# AD8368.net
KiCad netlist of a schematic drawn in Altium Designer
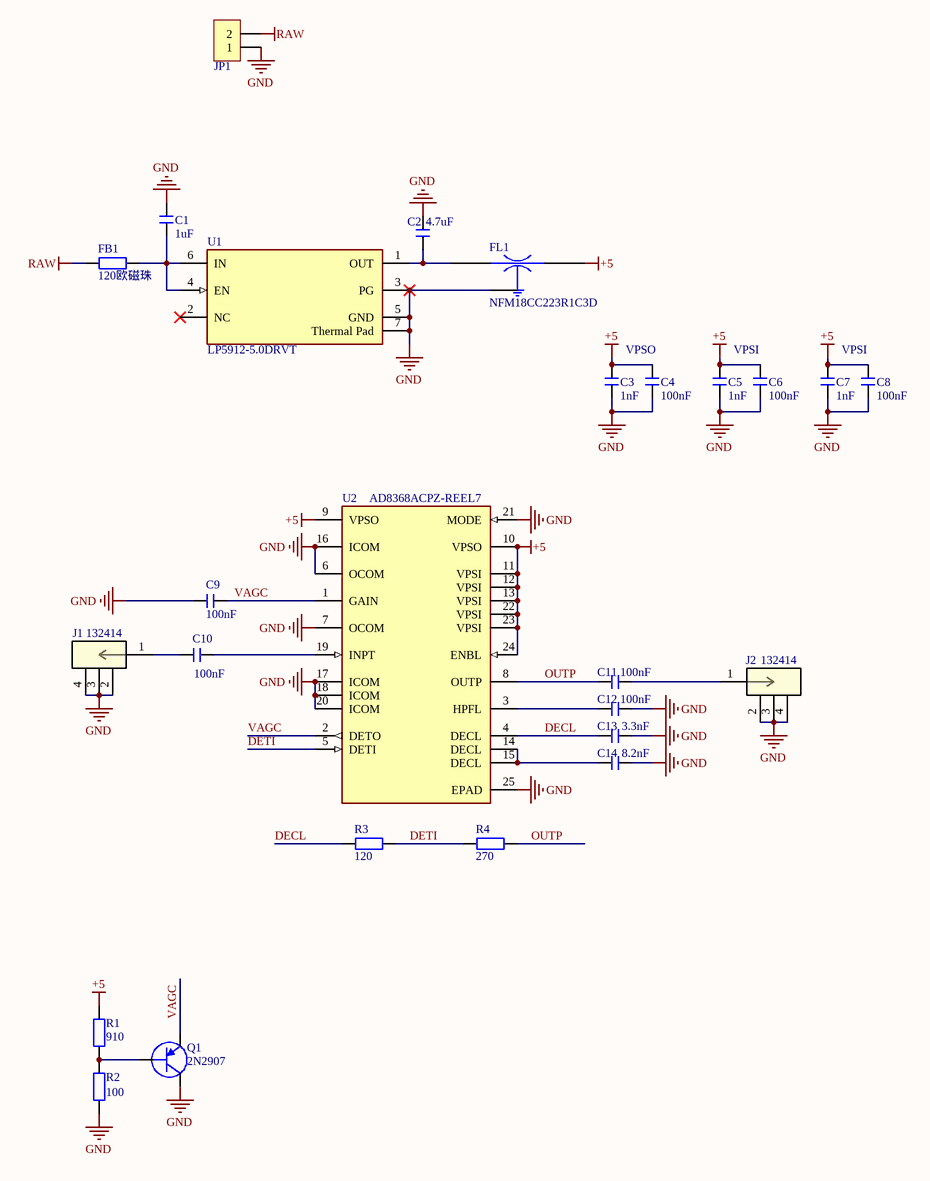
[diagram p0: AD8368.SchDoc]

(export (version "E")
  (design (tool "Eeschema 10.0.6"))
  (components
    (comp (ref "C1")
      (value "1uF")
      (footprint "C 0603_L")
      (description "贴片电容")
      (libsource (lib "01 - 电容-电阻-电感") (part "C"))
    )
    (comp (ref "C2")
      (value "4.7uF")
      (footprint "C 0603_L")
      (description "贴片电容")
      (libsource (lib "01 - 电容-电阻-电感") (part "C"))
    )
    (comp (ref "C3")
      (value "1nF")
      (footprint "C 0402_L")
      (description "贴片电容")
      (libsource (lib "01 - 电容-电阻-电感") (part "C"))
    )
    (comp (ref "C4")
      (value "100nF")
      (footprint "C 0402_L")
      (description "贴片电容")
      (libsource (lib "01 - 电容-电阻-电感") (part "C"))
    )
    (comp (ref "C5")
      (value "1nF")
      (footprint "C 0402_L")
      (description "贴片电容")
      (libsource (lib "01 - 电容-电阻-电感") (part "C"))
    )
    (comp (ref "C6")
      (value "100nF")
      (footprint "C 0402_L")
      (description "贴片电容")
      (libsource (lib "01 - 电容-电阻-电感") (part "C"))
    )
    (comp (ref "C7")
      (value "1nF")
      (footprint "C 0402_L")
      (description "贴片电容")
      (libsource (lib "01 - 电容-电阻-电感") (part "C"))
    )
    (comp (ref "C8")
      (value "100nF")
      (footprint "C 0402_L")
      (description "贴片电容")
      (libsource (lib "01 - 电容-电阻-电感") (part "C"))
    )
    (comp (ref "C9")
      (value "100nF")
      (footprint "C 0402_L")
      (description "贴片电容")
      (libsource (lib "01 - 电容-电阻-电感") (part "C"))
    )
    (comp (ref "C10")
      (value "100nF")
      (footprint "C 0402_L")
      (description "贴片电容")
      (libsource (lib "01 - 电容-电阻-电感") (part "C"))
    )
    (comp (ref "C11")
      (value "100nF")
      (footprint "C 0402_L")
      (description "贴片电容")
      (libsource (lib "01 - 电容-电阻-电感") (part "C"))
    )
    (comp (ref "C12")
      (value "100nF")
      (footprint "C 0402_L")
      (description "贴片电容")
      (libsource (lib "01 - 电容-电阻-电感") (part "C"))
    )
    (comp (ref "C13")
      (value "3.3nF")
      (footprint "C 0402_L")
      (description "贴片电容")
      (libsource (lib "01 - 电容-电阻-电感") (part "C"))
    )
    (comp (ref "C14")
      (value "8.2nF")
      (footprint "C 0402_L")
      (description "贴片电容")
      (libsource (lib "01 - 电容-电阻-电感") (part "C"))
    )
    (comp (ref "FB1")
      (value "120欧磁珠")
      (footprint "R 0603_L")
      (description "贴片电阻")
      (libsource (lib "01 - 电容-电阻-电感") (part "R"))
    )
    (comp (ref "FL1")
      (value "NFM18CC223R1C3D")
      (footprint "FIL_NFM18CC223R1C3D")
      (description "SMD Capacitor with Capacitance: 22000pF Tol. 20%. Rated Voltage: 16Vdc")
      (fields (field (name "MF") "Murata"))
      (libsource (lib "NFM18CC223R1C3D") (part "NFM18CC223R1C3D"))
    )
    (comp (ref "J1")
      (value "132414")
      (footprint "CONN_132414_AMP")
      (description "No Description Available")
      (fields (field (name "COPYRIGHT") "Copyright (C) 2022 Ultra Librarian. All rights reserved."))
      (libsource (lib "") (part "132414_1"))
    )
    (comp (ref "J2")
      (value "132414")
      (footprint "CONN_132414_AMP")
      (description "No Description Available")
      (fields (field (name "COPYRIGHT") "Copyright (C) 2022 Ultra Librarian. All rights reserved."))
      (libsource (lib "细针大偏脚SMA(用这个)") (part "132414"))
    )
    (comp (ref "JP1")
      (value "HDR-1X2")
      (footprint "KF2510-LI-2P")
      (description "2P接插件")
      (libsource (lib "18 - 接插件-脚距2.54mm (100mil) ") (part "Header 2"))
    )
    (comp (ref "Q1")
      (value "2N2907")
      (footprint "SOT23-3N")
      (description "PNP型三极管")
      (libsource (lib "02 - 二极管(LED)-三极管-整流桥") (part "2N-PNP"))
    )
    (comp (ref "R1")
      (value "910")
      (footprint "R 0402_L")
      (description "贴片电阻")
      (libsource (lib "01 - 电容-电阻-电感") (part "R"))
    )
    (comp (ref "R2")
      (value "100")
      (footprint "R 0402_L")
      (description "贴片电阻")
      (libsource (lib "01 - 电容-电阻-电感") (part "R"))
    )
    (comp (ref "R3")
      (value "120")
      (footprint "R 0603_L")
      (description "贴片电阻")
      (libsource (lib "01 - 电容-电阻-电感") (part "R"))
    )
    (comp (ref "R4")
      (value "270")
      (footprint "R 0603_L")
      (description "贴片电阻")
      (libsource (lib "01 - 电容-电阻-电感") (part "R"))
    )
    (comp (ref "U1")
      (value "LP5912-5.0DRVT")
      (footprint "FP-DRV0006A-MFG")
      (description "IC REG LINEAR  5.0V 500MA 6SON")
      (libsource (lib "LP5912") (part "LP5912"))
    )
    (comp (ref "U2")
      (value "AD8368ACPZ-REEL7")
      (footprint "FP-CP-24-7-IPC_C")
      (description "IC OPAMP VGA 1 CIRCUIT 24LFCSP")
      (libsource (lib "AD8368") (part "AD8368ACPZ-REEL7"))
    )
  )
  (nets
    (net (code "1") (name "+5") (class "Default")
      (node (ref "C3") (pin "2") (pinfunction "2_2") (pintype "passive"))
      (node (ref "C4") (pin "2") (pinfunction "2_2") (pintype "passive"))
      (node (ref "C5") (pin "2") (pinfunction "2_2") (pintype "passive"))
      (node (ref "C6") (pin "2") (pinfunction "2_2") (pintype "passive"))
      (node (ref "C7") (pin "2") (pinfunction "2_2") (pintype "passive"))
      (node (ref "C8") (pin "2") (pinfunction "2_2") (pintype "passive"))
      (node (ref "FL1") (pin "3") (pintype "passive"))
      (node (ref "R1") (pin "2") (pinfunction "2_2") (pintype "passive"))
      (node (ref "U2") (pin "10") (pinfunction "VPSO_10") (pintype "power_in"))
      (node (ref "U2") (pin "11") (pinfunction "VPSI_11") (pintype "power_in"))
      (node (ref "U2") (pin "12") (pinfunction "VPSI_12") (pintype "power_in"))
      (node (ref "U2") (pin "13") (pinfunction "VPSI_13") (pintype "power_in"))
      (node (ref "U2") (pin "22") (pinfunction "VPSI_22") (pintype "power_in"))
      (node (ref "U2") (pin "23") (pinfunction "VPSI_23") (pintype "power_in"))
      (node (ref "U2") (pin "24") (pinfunction "ENBL_24") (pintype "input"))
      (node (ref "U2") (pin "9") (pinfunction "VPSO_9") (pintype "power_in"))
    )
    (net (code "2") (name "/DECL") (class "Default")
      (node (ref "C13") (pin "1") (pinfunction "1_1") (pintype "passive"))
      (node (ref "R3") (pin "1") (pinfunction "1_1") (pintype "passive"))
      (node (ref "U2") (pin "4") (pinfunction "DECL_4") (pintype "passive"))
    )
    (net (code "3") (name "/DETI") (class "Default")
      (node (ref "R3") (pin "2") (pinfunction "2_2") (pintype "passive"))
      (node (ref "R4") (pin "1") (pinfunction "1_1") (pintype "passive"))
      (node (ref "U2") (pin "5") (pinfunction "DETI_5") (pintype "input"))
    )
    (net (code "4") (name "/OUTP") (class "Default")
      (node (ref "C11") (pin "1") (pinfunction "1_1") (pintype "passive"))
      (node (ref "R4") (pin "2") (pinfunction "2_2") (pintype "passive"))
      (node (ref "U2") (pin "8") (pinfunction "OUTP_8") (pintype "passive"))
    )
    (net (code "5") (name "/VAGC") (class "Default")
      (node (ref "C9") (pin "2") (pinfunction "2_2") (pintype "passive"))
      (node (ref "Q1") (pin "1") (pinfunction "E_1") (pintype "passive"))
      (node (ref "U2") (pin "1") (pinfunction "GAIN_1") (pintype "passive"))
      (node (ref "U2") (pin "2") (pinfunction "DETO_2") (pintype "output"))
    )
    (net (code "6") (name "GND") (class "Default")
      (node (ref "C1") (pin "2") (pinfunction "2_2") (pintype "passive"))
      (node (ref "C12") (pin "2") (pinfunction "2_2") (pintype "passive"))
      (node (ref "C13") (pin "2") (pinfunction "2_2") (pintype "passive"))
      (node (ref "C14") (pin "2") (pinfunction "2_2") (pintype "passive"))
      (node (ref "C2") (pin "2") (pinfunction "2_2") (pintype "passive"))
      (node (ref "C3") (pin "1") (pinfunction "1_1") (pintype "passive"))
      (node (ref "C4") (pin "1") (pinfunction "1_1") (pintype "passive"))
      (node (ref "C5") (pin "1") (pinfunction "1_1") (pintype "passive"))
      (node (ref "C6") (pin "1") (pinfunction "1_1") (pintype "passive"))
      (node (ref "C7") (pin "1") (pinfunction "1_1") (pintype "passive"))
      (node (ref "C8") (pin "1") (pinfunction "1_1") (pintype "passive"))
      (node (ref "C9") (pin "1") (pinfunction "1_1") (pintype "passive"))
      (node (ref "FL1") (pin "2") (pinfunction "GND_2") (pintype "power_in"))
      (node (ref "J1") (pin "2") (pinfunction "2_2") (pintype "passive"))
      (node (ref "J1") (pin "3") (pinfunction "3_3") (pintype "passive"))
      (node (ref "J1") (pin "4") (pinfunction "4_4") (pintype "passive"))
      (node (ref "J2") (pin "2") (pinfunction "2_2") (pintype "passive"))
      (node (ref "J2") (pin "3") (pinfunction "3_3") (pintype "passive"))
      (node (ref "J2") (pin "4") (pinfunction "4_4") (pintype "passive"))
      (node (ref "JP1") (pin "1") (pinfunction "1_1") (pintype "passive"))
      (node (ref "Q1") (pin "3") (pinfunction "C_3") (pintype "passive"))
      (node (ref "R2") (pin "1") (pinfunction "1_1") (pintype "passive"))
      (node (ref "U1") (pin "3") (pinfunction "PG_3") (pintype "open_collector"))
      (node (ref "U1") (pin "5") (pinfunction "GND_5") (pintype "power_in"))
      (node (ref "U1") (pin "7") (pinfunction "Thermal_Pad_7") (pintype "power_in"))
      (node (ref "U2") (pin "16") (pinfunction "ICOM_16") (pintype "passive"))
      (node (ref "U2") (pin "17") (pinfunction "ICOM_17") (pintype "passive"))
      (node (ref "U2") (pin "18") (pinfunction "ICOM_18") (pintype "passive"))
      (node (ref "U2") (pin "20") (pinfunction "ICOM_20") (pintype "passive"))
      (node (ref "U2") (pin "21") (pinfunction "MODE_21") (pintype "input"))
      (node (ref "U2") (pin "25") (pinfunction "EPAD_25") (pintype "passive"))
      (node (ref "U2") (pin "6") (pinfunction "OCOM_6") (pintype "passive"))
      (node (ref "U2") (pin "7") (pinfunction "OCOM_7") (pintype "passive"))
    )
    (net (code "7") (name "Net-(C10-Pad1)") (class "Default")
      (node (ref "C10") (pin "1") (pinfunction "1_1") (pintype "passive"))
      (node (ref "J1") (pin "1") (pinfunction "1_1") (pintype "passive"))
    )
    (net (code "8") (name "Net-(C11-Pad2)") (class "Default")
      (node (ref "C11") (pin "2") (pinfunction "2_2") (pintype "passive"))
      (node (ref "J2") (pin "1") (pinfunction "1_1") (pintype "passive"))
    )
    (net (code "9") (name "Net-(C14-Pad1)") (class "Default")
      (node (ref "C14") (pin "1") (pinfunction "1_1") (pintype "passive"))
      (node (ref "U2") (pin "14") (pinfunction "DECL_14") (pintype "passive"))
      (node (ref "U2") (pin "15") (pinfunction "DECL_15") (pintype "passive"))
    )
    (net (code "10") (name "Net-(Q1-B)") (class "Default")
      (node (ref "Q1") (pin "2") (pinfunction "B_2") (pintype "passive"))
      (node (ref "R1") (pin "1") (pinfunction "1_1") (pintype "passive"))
      (node (ref "R2") (pin "2") (pinfunction "2_2") (pintype "passive"))
    )
    (net (code "11") (name "Net-(U1-EN)") (class "Default")
      (node (ref "C1") (pin "1") (pinfunction "1_1") (pintype "passive"))
      (node (ref "FB1") (pin "2") (pinfunction "2_2") (pintype "passive"))
      (node (ref "U1") (pin "4") (pinfunction "EN_4") (pintype "input"))
      (node (ref "U1") (pin "6") (pinfunction "IN_6") (pintype "power_in"))
    )
    (net (code "12") (name "Net-(U1-OUT)") (class "Default")
      (node (ref "C2") (pin "1") (pinfunction "1_1") (pintype "passive"))
      (node (ref "FL1") (pin "1") (pintype "passive"))
      (node (ref "U1") (pin "1") (pinfunction "OUT_1") (pintype "power_in"))
    )
    (net (code "13") (name "Net-(U2-HPFL)") (class "Default")
      (node (ref "C12") (pin "1") (pinfunction "1_1") (pintype "passive"))
      (node (ref "U2") (pin "3") (pinfunction "HPFL_3") (pintype "passive"))
    )
    (net (code "14") (name "Net-(U2-INPT)") (class "Default")
      (node (ref "C10") (pin "2") (pinfunction "2_2") (pintype "passive"))
      (node (ref "U2") (pin "19") (pinfunction "INPT_19") (pintype "input"))
    )
    (net (code "15") (name "RAW") (class "Default")
      (node (ref "FB1") (pin "1") (pinfunction "1_1") (pintype "passive"))
      (node (ref "JP1") (pin "2") (pinfunction "2_2") (pintype "passive"))
    )
    (net (code "16") (name "unconnected-(U1-NC-Pad2)") (class "Default")
      (node (ref "U1") (pin "2") (pinfunction "NC_2") (pintype "passive+no_connect"))
    )
  )
)
